# LED_indicators_6W.net
KiCad netlist of a schematic drawn in Altium Designer
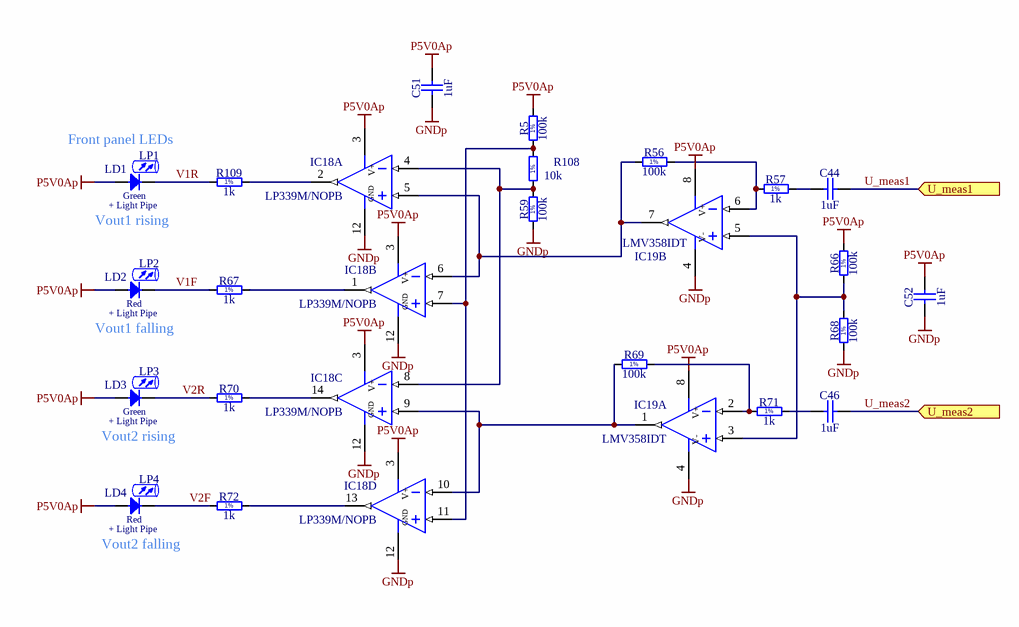
[diagram p0: LED_indicators_6W.SchDoc]

(export (version "E")
  (design (tool "Eeschema 10.0.6"))
  (components
    (comp (ref "C44")
      (value "1uF")
      (footprint "CAPC1005X55N")
      (description "Non-polarised capacitor")
      (fields
        (field (name "PART NUMBER") "CC0402_1UF_16V_10%_X5R")
        (field (name "VOLTAGE") "16V")
        (field (name "AUTHOR") "CERN DEM JLC")
      )
      (libsource (lib "Capacitors") (part "Capacitor - non polarized"))
    )
    (comp (ref "C46")
      (value "1uF")
      (footprint "CAPC1005X55N")
      (description "Non-polarised capacitor")
      (fields
        (field (name "PART NUMBER") "CC0402_1UF_16V_10%_X5R")
        (field (name "VOLTAGE") "16V")
        (field (name "AUTHOR") "CERN DEM JLC")
      )
      (libsource (lib "Capacitors") (part "Capacitor - non polarized"))
    )
    (comp (ref "C51")
      (value "1uF")
      (footprint "CAPC1005X55N")
      (description "Non-polarised capacitor")
      (fields
        (field (name "PART NUMBER") "CC0402_1UF_16V_10%_X5R")
        (field (name "VOLTAGE") "16V")
        (field (name "AUTHOR") "CERN DEM JLC")
      )
      (libsource (lib "Capacitors") (part "Capacitor - non polarized"))
    )
    (comp (ref "C52")
      (value "1uF")
      (footprint "CAPC1005X55N")
      (description "Non-polarised capacitor")
      (fields
        (field (name "PART NUMBER") "CC0402_1UF_16V_10%_X5R")
        (field (name "VOLTAGE") "16V")
        (field (name "AUTHOR") "CERN DEM JLC")
      )
      (libsource (lib "Capacitors") (part "Capacitor - non polarized"))
    )
    (comp (ref "IC18")
      (value "LP339M/NOPB")
      (footprint "SOIC127P600X175-14N")
      (description "Quad Operational Amplifier")
      (fields (field (name "MANUFACTURER") "TEXAS INSTRUMENTS") (field (name "AUTHOR") "CERN DEM MR"))
      (libsource (lib "ICs And Semiconductors") (part "Operational Amplifier x4 Type5"))
    )
    (comp (ref "IC19")
      (value "LMV358IDT")
      (footprint "SOIC127P600X175-8N")
      (description "Dual Operational Amplifier")
      (fields (field (name "MANUFACTURER") "ST MICROELECTRONICS") (field (name "AUTHOR") "CERN DEM HF"))
      (libsource (lib "ICs And Semiconductors") (part "Operational Amplifier x2 Type1"))
    )
    (comp (ref "LD1")
      (value "Green")
      (footprint "LED_DIALIGHT_555-230")
      (description "LED Green 1C 2A")
      (fields
        (field (name "PART NUMBER") "LED_DIALIGHT_555-2301F")
        (field (name "MANUFACTURER") "DIALIGHT")
        (field (name "AUTHOR") "CERN DEM JMW")
      )
      (libsource (lib "ICs And Semiconductors") (part "LED Green 1C 2A"))
    )
    (comp (ref "LD2")
      (value "Red")
      (footprint "LED_DIALIGHT_555-200")
      (description "LED Red 1C 2A")
      (fields
        (field (name "PART NUMBER") "LED_DIALIGHT_555-2001F")
        (field (name "MANUFACTURER") "DIALIGHT")
        (field (name "AUTHOR") "CERN DEM JMW")
      )
      (libsource (lib "ICs And Semiconductors") (part "LED Red 1C 2A"))
    )
    (comp (ref "LD3")
      (value "Green")
      (footprint "LED_DIALIGHT_555-230")
      (description "LED Green 1C 2A")
      (fields
        (field (name "PART NUMBER") "LED_DIALIGHT_555-2301F")
        (field (name "MANUFACTURER") "DIALIGHT")
        (field (name "AUTHOR") "CERN DEM JMW")
      )
      (libsource (lib "ICs And Semiconductors") (part "LED Green 1C 2A"))
    )
    (comp (ref "LD4")
      (value "Red")
      (footprint "LED_DIALIGHT_555-200")
      (description "LED Red 1C 2A")
      (fields
        (field (name "PART NUMBER") "LED_DIALIGHT_555-2001F")
        (field (name "MANUFACTURER") "DIALIGHT")
        (field (name "AUTHOR") "CERN DEM JMW")
      )
      (libsource (lib "ICs And Semiconductors") (part "LED Red 1C 2A"))
    )
    (comp (ref "LP1")
      (value "~")
      (footprint "LEDLP_BIVAR_PLP2-1200")
      (description "LED Light Pipe x1 Type1")
      (fields
        (field (name "PART NUMBER") "LEDLP_BIVAR_PLP2-1200")
        (field (name "MANUFACTURER") "BIVAR")
        (field (name "AUTHOR") "CERN DEM HF")
      )
      (libsource (lib "ICs And Semiconductors") (part "LED Light Pipe x1 Type1"))
    )
    (comp (ref "LP2")
      (value "~")
      (footprint "LEDLP_BIVAR_PLP2-1200")
      (description "LED Light Pipe x1 Type1")
      (fields
        (field (name "PART NUMBER") "LEDLP_BIVAR_PLP2-1200")
        (field (name "MANUFACTURER") "BIVAR")
        (field (name "AUTHOR") "CERN DEM HF")
      )
      (libsource (lib "ICs And Semiconductors") (part "LED Light Pipe x1 Type1"))
    )
    (comp (ref "LP3")
      (value "~")
      (footprint "LEDLP_BIVAR_PLP2-1200")
      (description "LED Light Pipe x1 Type1")
      (fields
        (field (name "PART NUMBER") "LEDLP_BIVAR_PLP2-1200")
        (field (name "MANUFACTURER") "BIVAR")
        (field (name "AUTHOR") "CERN DEM HF")
      )
      (libsource (lib "ICs And Semiconductors") (part "LED Light Pipe x1 Type1"))
    )
    (comp (ref "LP4")
      (value "~")
      (footprint "LEDLP_BIVAR_PLP2-1200")
      (description "LED Light Pipe x1 Type1")
      (fields
        (field (name "PART NUMBER") "LEDLP_BIVAR_PLP2-1200")
        (field (name "MANUFACTURER") "BIVAR")
        (field (name "AUTHOR") "CERN DEM HF")
      )
      (libsource (lib "ICs And Semiconductors") (part "LED Light Pipe x1 Type1"))
    )
    (comp (ref "R5")
      (value "100k")
      (footprint "RESC1608X55N")
      (description "Resistor - 1%")
      (fields
        (field (name "PART NUMBER") "R0603_100K_1%_0.1W_100PPM")
        (field (name "POWER") "0.1W")
        (field (name "AUTHOR") "CERN DEM JLC")
      )
      (libsource (lib "Resistors") (part "Resistor - 1%"))
    )
    (comp (ref "R56")
      (value "100k")
      (footprint "RESC1608X55N")
      (description "Resistor - 1%")
      (fields
        (field (name "PART NUMBER") "R0603_100K_1%_0.1W_100PPM")
        (field (name "POWER") "0.1W")
        (field (name "AUTHOR") "CERN DEM JLC")
      )
      (libsource (lib "Resistors") (part "Resistor - 1%"))
    )
    (comp (ref "R57")
      (value "1k")
      (footprint "RESC1005X40N")
      (description "Resistor - 1%")
      (fields
        (field (name "PART NUMBER") "R0402_1K_1%_0.0625W_100PPM")
        (field (name "POWER") "0.0625W")
        (field (name "AUTHOR") "CERN DEM JLC")
      )
      (libsource (lib "Resistors") (part "Resistor - 1%"))
    )
    (comp (ref "R59")
      (value "100k")
      (footprint "RESC1608X55N")
      (description "Resistor - 1%")
      (fields
        (field (name "PART NUMBER") "R0603_100K_1%_0.1W_100PPM")
        (field (name "POWER") "0.1W")
        (field (name "AUTHOR") "CERN DEM JLC")
      )
      (libsource (lib "Resistors") (part "Resistor - 1%"))
    )
    (comp (ref "R66")
      (value "100k")
      (footprint "RESC1608X55N")
      (description "Resistor - 1%")
      (fields
        (field (name "PART NUMBER") "R0603_100K_1%_0.1W_100PPM")
        (field (name "POWER") "0.1W")
        (field (name "AUTHOR") "CERN DEM JLC")
      )
      (libsource (lib "Resistors") (part "Resistor - 1%"))
    )
    (comp (ref "R67")
      (value "1k")
      (footprint "RESC1005X40N")
      (description "Resistor - 1%")
      (fields
        (field (name "PART NUMBER") "R0402_1K_1%_0.0625W_100PPM")
        (field (name "POWER") "0.0625W")
        (field (name "AUTHOR") "CERN DEM JLC")
      )
      (libsource (lib "Resistors") (part "Resistor - 1%"))
    )
    (comp (ref "R68")
      (value "100k")
      (footprint "RESC1608X55N")
      (description "Resistor - 1%")
      (fields
        (field (name "PART NUMBER") "R0603_100K_1%_0.1W_100PPM")
        (field (name "POWER") "0.1W")
        (field (name "AUTHOR") "CERN DEM JLC")
      )
      (libsource (lib "Resistors") (part "Resistor - 1%"))
    )
    (comp (ref "R69")
      (value "100k")
      (footprint "RESC1608X55N")
      (description "Resistor - 1%")
      (fields
        (field (name "PART NUMBER") "R0603_100K_1%_0.1W_100PPM")
        (field (name "POWER") "0.1W")
        (field (name "AUTHOR") "CERN DEM JLC")
      )
      (libsource (lib "Resistors") (part "Resistor - 1%"))
    )
    (comp (ref "R70")
      (value "1k")
      (footprint "RESC1005X40N")
      (description "Resistor - 1%")
      (fields
        (field (name "PART NUMBER") "R0402_1K_1%_0.0625W_100PPM")
        (field (name "POWER") "0.0625W")
        (field (name "AUTHOR") "CERN DEM JLC")
      )
      (libsource (lib "Resistors") (part "Resistor - 1%"))
    )
    (comp (ref "R71")
      (value "1k")
      (footprint "RESC1005X40N")
      (description "Resistor - 1%")
      (fields
        (field (name "PART NUMBER") "R0402_1K_1%_0.0625W_100PPM")
        (field (name "POWER") "0.0625W")
        (field (name "AUTHOR") "CERN DEM JLC")
      )
      (libsource (lib "Resistors") (part "Resistor - 1%"))
    )
    (comp (ref "R72")
      (value "1k")
      (footprint "RESC1005X40N")
      (description "Resistor - 1%")
      (fields
        (field (name "PART NUMBER") "R0402_1K_1%_0.0625W_100PPM")
        (field (name "POWER") "0.0625W")
        (field (name "AUTHOR") "CERN DEM JLC")
      )
      (libsource (lib "Resistors") (part "Resistor - 1%"))
    )
    (comp (ref "R108")
      (value "10k")
      (footprint "RESC1005X40N")
      (description "Resistor - 1%")
      (fields
        (field (name "PART NUMBER") "R0402_10K_1%_0.0625W_100PPM")
        (field (name "POWER") "0.0625W")
        (field (name "AUTHOR") "CERN DEM JLC")
      )
      (libsource (lib "Resistors") (part "Resistor - 1%"))
    )
    (comp (ref "R109")
      (value "1k")
      (footprint "RESC1005X40N")
      (description "Resistor - 1%")
      (fields
        (field (name "PART NUMBER") "R0402_1K_1%_0.0625W_100PPM")
        (field (name "POWER") "0.0625W")
        (field (name "AUTHOR") "CERN DEM JLC")
      )
      (libsource (lib "Resistors") (part "Resistor - 1%"))
    )
  )
  (nets
    (net (code "1") (name "/U_meas1") (class "Default")
      (node (ref "C44") (pin "2") (pinfunction "2_2") (pintype "passive"))
    )
    (net (code "2") (name "/U_meas2") (class "Default")
      (node (ref "C46") (pin "2") (pinfunction "2_2") (pintype "passive"))
    )
    (net (code "3") (name "/V1F") (class "Default")
      (node (ref "LD2") (pin "1") (pinfunction "C_1") (pintype "passive"))
      (node (ref "R67") (pin "1") (pinfunction "1_1") (pintype "passive"))
    )
    (net (code "4") (name "/V1R") (class "Default")
      (node (ref "LD1") (pin "1") (pinfunction "C_1") (pintype "passive"))
      (node (ref "R109") (pin "1") (pinfunction "1_1") (pintype "passive"))
    )
    (net (code "5") (name "/V2F") (class "Default")
      (node (ref "LD4") (pin "1") (pinfunction "C_1") (pintype "passive"))
      (node (ref "R72") (pin "1") (pinfunction "1_1") (pintype "passive"))
    )
    (net (code "6") (name "/V2R") (class "Default")
      (node (ref "LD3") (pin "1") (pinfunction "C_1") (pintype "passive"))
      (node (ref "R70") (pin "1") (pinfunction "1_1") (pintype "passive"))
    )
    (net (code "7") (name "GNDp") (class "Default")
      (node (ref "C51") (pin "1") (pinfunction "1_1") (pintype "passive"))
      (node (ref "C52") (pin "1") (pinfunction "1_1") (pintype "passive"))
      (node (ref "IC18") (pin "12") (pinfunction "GND_12") (pintype "power_in"))
      (node (ref "IC19") (pin "4") (pinfunction "V-_4") (pintype "power_in"))
      (node (ref "R59") (pin "1") (pinfunction "1_1") (pintype "passive"))
      (node (ref "R68") (pin "1") (pinfunction "1_1") (pintype "passive"))
    )
    (net (code "8") (name "Net-(C44-Pad1)") (class "Default")
      (node (ref "C44") (pin "1") (pinfunction "1_1") (pintype "passive"))
      (node (ref "R57") (pin "2") (pinfunction "2_2") (pintype "passive"))
    )
    (net (code "9") (name "Net-(C46-Pad1)") (class "Default")
      (node (ref "C46") (pin "1") (pinfunction "1_1") (pintype "passive"))
      (node (ref "R71") (pin "2") (pinfunction "2_2") (pintype "passive"))
    )
    (net (code "10") (name "Net-(IC18A-IN+)") (class "Default")
      (node (ref "IC18") (pin "5") (pinfunction "IN+_5") (pintype "input"))
      (node (ref "IC18") (pin "6") (pinfunction "IN-_6") (pintype "input"))
      (node (ref "IC19") (pin "7") (pinfunction "OUT_7") (pintype "output"))
      (node (ref "R56") (pin "1") (pinfunction "1_1") (pintype "passive"))
    )
    (net (code "11") (name "Net-(IC18A-IN-)") (class "Default")
      (node (ref "IC18") (pin "4") (pinfunction "IN-_4") (pintype "input"))
      (node (ref "IC18") (pin "8") (pinfunction "IN-_8") (pintype "input"))
      (node (ref "R108") (pin "1") (pinfunction "1_1") (pintype "passive"))
      (node (ref "R59") (pin "2") (pinfunction "2_2") (pintype "passive"))
    )
    (net (code "12") (name "Net-(IC18A-OUT)") (class "Default")
      (node (ref "IC18") (pin "2") (pinfunction "OUT_2") (pintype "output"))
      (node (ref "R109") (pin "2") (pinfunction "2_2") (pintype "passive"))
    )
    (net (code "13") (name "Net-(IC18B-IN+)") (class "Default")
      (node (ref "IC18") (pin "11") (pinfunction "IN+_11") (pintype "input"))
      (node (ref "IC18") (pin "7") (pinfunction "IN+_7") (pintype "input"))
      (node (ref "R108") (pin "2") (pinfunction "2_2") (pintype "passive"))
      (node (ref "R5") (pin "1") (pinfunction "1_1") (pintype "passive"))
    )
    (net (code "14") (name "Net-(IC18B-OUT)") (class "Default")
      (node (ref "IC18") (pin "1") (pinfunction "OUT_1") (pintype "output"))
      (node (ref "R67") (pin "2") (pinfunction "2_2") (pintype "passive"))
    )
    (net (code "15") (name "Net-(IC18C-IN+)") (class "Default")
      (node (ref "IC18") (pin "10") (pinfunction "IN-_10") (pintype "input"))
      (node (ref "IC18") (pin "9") (pinfunction "IN+_9") (pintype "input"))
      (node (ref "IC19") (pin "1") (pinfunction "OUT_1") (pintype "output"))
      (node (ref "R69") (pin "1") (pinfunction "1_1") (pintype "passive"))
    )
    (net (code "16") (name "Net-(IC18C-OUT)") (class "Default")
      (node (ref "IC18") (pin "14") (pinfunction "OUT_14") (pintype "output"))
      (node (ref "R70") (pin "2") (pinfunction "2_2") (pintype "passive"))
    )
    (net (code "17") (name "Net-(IC18D-OUT)") (class "Default")
      (node (ref "IC18") (pin "13") (pinfunction "OUT_13") (pintype "output"))
      (node (ref "R72") (pin "2") (pinfunction "2_2") (pintype "passive"))
    )
    (net (code "18") (name "Net-(IC19A-IN+)") (class "Default")
      (node (ref "IC19") (pin "3") (pinfunction "IN+_3") (pintype "input"))
      (node (ref "IC19") (pin "5") (pinfunction "IN+_5") (pintype "input"))
      (node (ref "R66") (pin "1") (pinfunction "1_1") (pintype "passive"))
      (node (ref "R68") (pin "2") (pinfunction "2_2") (pintype "passive"))
    )
    (net (code "19") (name "Net-(IC19A-IN-)") (class "Default")
      (node (ref "IC19") (pin "2") (pinfunction "IN-_2") (pintype "input"))
      (node (ref "R69") (pin "2") (pinfunction "2_2") (pintype "passive"))
      (node (ref "R71") (pin "1") (pinfunction "1_1") (pintype "passive"))
    )
    (net (code "20") (name "Net-(IC19B-IN-)") (class "Default")
      (node (ref "IC19") (pin "6") (pinfunction "IN-_6") (pintype "input"))
      (node (ref "R56") (pin "2") (pinfunction "2_2") (pintype "passive"))
      (node (ref "R57") (pin "1") (pinfunction "1_1") (pintype "passive"))
    )
    (net (code "21") (name "P5V0Ap") (class "Default")
      (node (ref "C51") (pin "2") (pinfunction "2_2") (pintype "passive"))
      (node (ref "C52") (pin "2") (pinfunction "2_2") (pintype "passive"))
      (node (ref "IC18") (pin "3") (pinfunction "V+_3") (pintype "power_in"))
      (node (ref "IC19") (pin "8") (pinfunction "V+_8") (pintype "power_in"))
      (node (ref "LD1") (pin "2") (pinfunction "A_2") (pintype "passive"))
      (node (ref "LD2") (pin "2") (pinfunction "A_2") (pintype "passive"))
      (node (ref "LD3") (pin "2") (pinfunction "A_2") (pintype "passive"))
      (node (ref "LD4") (pin "2") (pinfunction "A_2") (pintype "passive"))
      (node (ref "R5") (pin "2") (pinfunction "2_2") (pintype "passive"))
      (node (ref "R66") (pin "2") (pinfunction "2_2") (pintype "passive"))
    )
  )
)
